# JacdacJoystick_44.net
KiCad netlist of a schematic drawn in Altium Designer
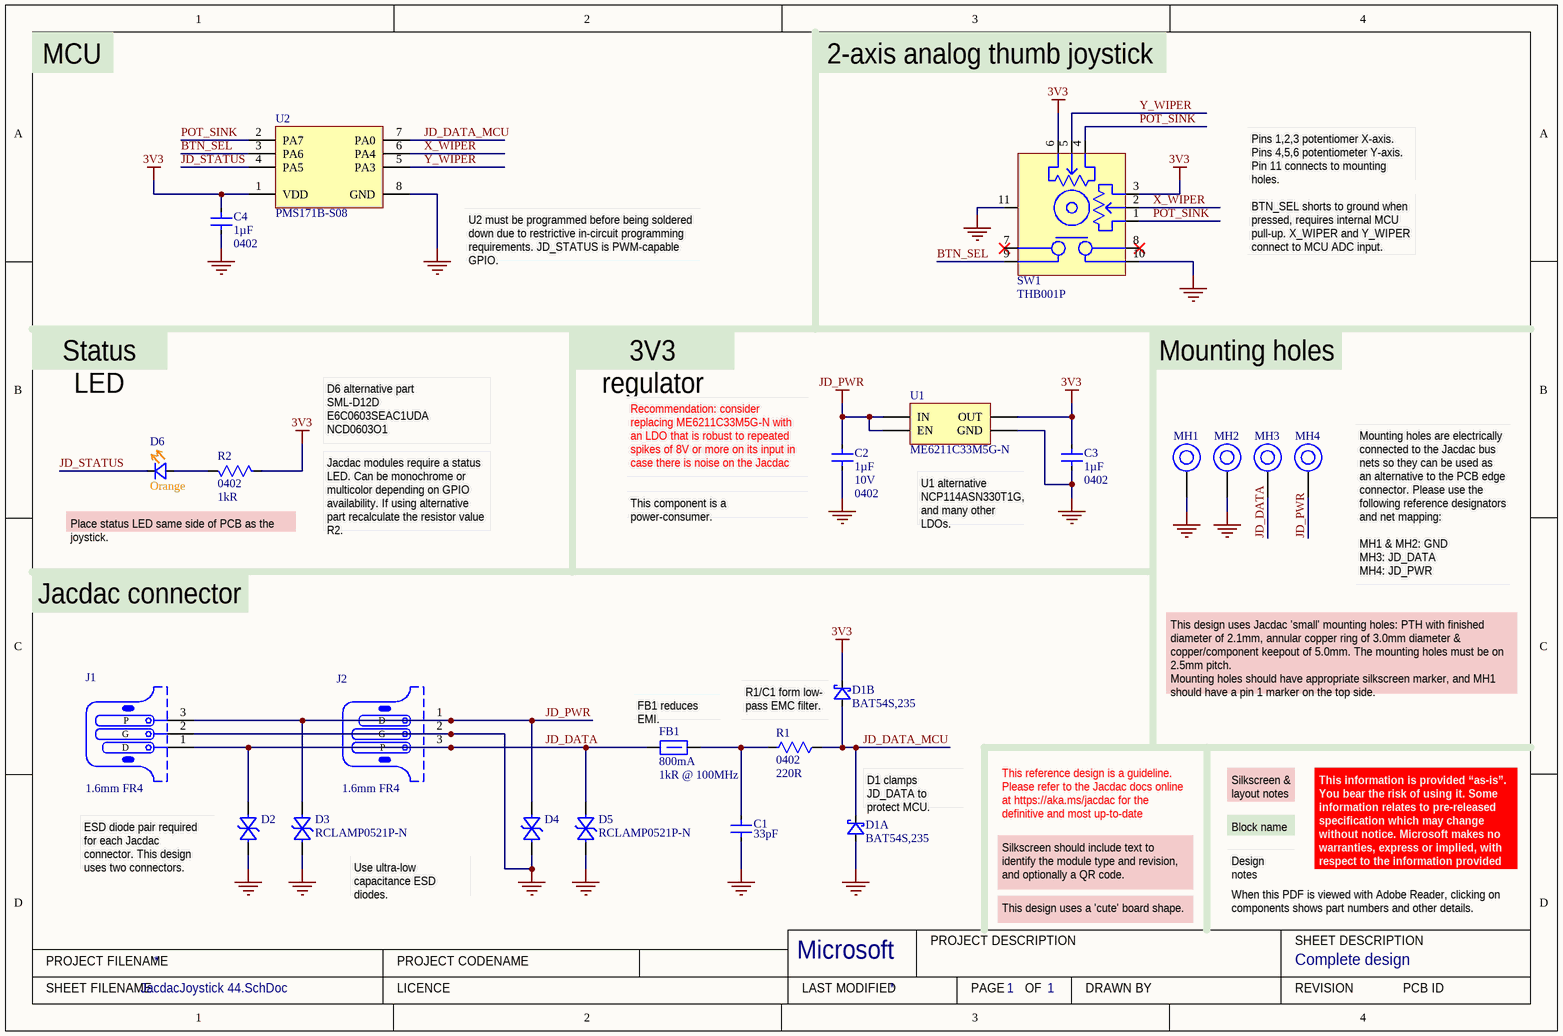
[diagram p0: JacdacJoystick 44.SchDoc]

(export (version "E")
  (design (tool "Eeschema 10.0.6"))
  (components
    (comp (ref "C1")
      (value "CL05C330JB5NNNC")
      (footprint "C0402_0.55MM - without outline")
      (description "CAP CER 33PF 50V C0G/NP0 0402")
      (fields
        (field (name "MANUFACTURER") "Samsung")
        (field (name "TOLERANCE") "5%")
        (field (name "CAPACITANCE") "33pF")
      )
      (libsource (lib "Samsung") (part "CL05C330JB5NNNC"))
    )
    (comp (ref "C2")
      (value "CL05A105KP5NNNC")
      (footprint "C0402_0.55MM - without outline")
      (description "CAP CER 1UF 10V X5R 0402")
      (fields
        (field (name "MANUFACTURER") "Samsung")
        (field (name "TOLERANCE") "10%")
        (field (name "CAPACITANCE") "1µF")
        (field (name "VOLTAGE RATING") "10V")
        (field (name "CASE CODE (IMPERIAL)") "0402")
        (field (name "CREATED") "DG")
        (field (name "CHECKED") "?")
      )
      (libsource (lib "Samsung") (part "CL05A105KP5NNNC"))
    )
    (comp (ref "C3")
      (value "CL05A105KP5NNNC")
      (footprint "C0402_0.55MM - without outline")
      (description "CAP CER 1UF 10V X5R 0402")
      (fields
        (field (name "MANUFACTURER") "Samsung")
        (field (name "TOLERANCE") "10%")
        (field (name "CAPACITANCE") "1µF")
        (field (name "CASE CODE (IMPERIAL)") "0402")
        (field (name "CREATED") "DG")
        (field (name "CHECKED") "?")
      )
      (libsource (lib "Samsung") (part "CL05A105KP5NNNC"))
    )
    (comp (ref "C4")
      (value "CL05A105KP5NNNC")
      (footprint "C0402_0.55MM - without outline")
      (description "CAP CER 1UF 10V X5R 0402")
      (fields
        (field (name "MANUFACTURER") "Samsung")
        (field (name "TOLERANCE") "10%")
        (field (name "CAPACITANCE") "1µF")
        (field (name "CASE CODE (IMPERIAL)") "0402")
        (field (name "CREATED") "DG")
        (field (name "CHECKED") "?")
      )
      (libsource (lib "Samsung") (part "CL05A105KP5NNNC"))
    )
    (comp (ref "D1")
      (value "BAT54S")
      (footprint "NXP-BAT54S-TO-236AB - without outline")
      (description "DIODE ARRAY SCHOTTKY 30V SOT23")
      (fields (field (name "MANUFACTURER") "Nexperia") (field (name "MANUFACTURER PART NUMBER") "BAT54S,235"))
      (libsource (lib "NXP") (part "BAT54S"))
    )
    (comp (ref "D2")
      (value "RCLAMP0521P-N")
      (footprint "TVS 0402 - L")
      (description "Bidirectional 5V (Max) 6V 16V 3.5A (8/20us) 0402 TVS RoHS")
      (fields
        (field (name "MANUFACTURER") "Born Semiconductor")
        (field (name "CREATED BY") "D Gakure")
        (field (name "CHECKED BY") "?")
      )
      (libsource (lib "BornSemiconductor") (part "RCLAMP0521P-N"))
    )
    (comp (ref "D3")
      (value "RCLAMP0521P-N")
      (footprint "TVS 0402 - L")
      (description "Bidirectional 5V (Max) 6V 16V 3.5A (8/20us) 0402 TVS RoHS")
      (fields
        (field (name "MANUFACTURER") "Born Semiconductor")
        (field (name "MANUFACTURER PART NUMBER") "RCLAMP0521P-N")
        (field (name "CREATED BY") "D Gakure")
        (field (name "CHECKED BY") "?")
      )
      (libsource (lib "BornSemiconductor") (part "RCLAMP0521P-N"))
    )
    (comp (ref "D4")
      (value "RCLAMP0521P-N")
      (footprint "TVS 0402 - L")
      (description "Bidirectional 5V (Max) 6V 16V 3.5A (8/20us) 0402 TVS RoHS")
      (fields
        (field (name "MANUFACTURER") "Born Semiconductor")
        (field (name "CREATED BY") "D Gakure")
        (field (name "CHECKED BY") "?")
      )
      (libsource (lib "BornSemiconductor") (part "RCLAMP0521P-N"))
    )
    (comp (ref "D5")
      (value "RCLAMP0521P-N")
      (footprint "TVS 0402 - L")
      (description "Bidirectional 5V (Max) 6V 16V 3.5A (8/20us) 0402 TVS RoHS")
      (fields
        (field (name "MANUFACTURER") "Born Semiconductor")
        (field (name "MANUFACTURER PART NUMBER") "RCLAMP0521P-N")
        (field (name "CREATED BY") "D Gakure")
        (field (name "CHECKED BY") "?")
      )
      (libsource (lib "BornSemiconductor") (part "RCLAMP0521P-N"))
    )
    (comp (ref "D6")
      (value "~")
      (footprint "0603 Orange")
      (description "LED ORANGE DIFFUSED 0603 SMD")
      (fields
        (field (name "MANUFACTURER") "Everlight Elec")
        (field (name "MANUFACTURER PART NUMBER") "19-217/S2C-AQ1R1B/3T")
        (field (name "COLOUR") "Orange")
      )
      (libsource (lib "EverlightElec") (part "19-217/S2C-AQ1R1B/3T"))
    )
    (comp (ref "FB1")
      (value "TDK MPZ1608S102ATA00")
      (footprint "TDK MPZ1608 0.8mm - without outline")
      (description "0603 1k@100MHz 0.8A chip")
      (fields
        (field (name "TOLERANCE") "25%")
        (field (name "MANUFACTURER") "TDK")
        (field (name "CURRENT RATING") "800mA")
        (field (name "IMPEDANCE") "1kR @ 100MHz")
      )
      (libsource (lib "TDK") (part "TDK MPZ1608S102ATA00"))
    )
    (comp (ref "J1")
      (value "3 pin JACDAC edge connector")
      (footprint "JACDAC_EDGE_CONNECTOR_NO_TRACES")
      (description "3 pin Jacdac edge connector 1.27mm pitch")
      (fields
        (field (name "MANUFACTURER PART NUMBER") "JACDAC_EDGE_CONNECTOR")
        (field (name "PCB TYPE") "1.6mm FR4")
        (field (name "CHECKED BY") "?")
        (field (name "CREATED BY") "D. Gakure")
      )
      (libsource (lib "generic-con") (part "Jacdac edge connector"))
    )
    (comp (ref "J2")
      (value "3 pin JACDAC edge connector")
      (footprint "JACDAC_EDGE_CONNECTOR_NO_TRACES")
      (description "3 pin Jacdac edge connector 1.27mm pitch")
      (fields
        (field (name "MANUFACTURER PART NUMBER") "JACDAC_EDGE_CONNECTOR")
        (field (name "PCB TYPE") "1.6mm FR4")
        (field (name "CHECKED BY") "?")
        (field (name "CREATED BY") "D. Gakure")
      )
      (libsource (lib "") (part "Jacdac edge connector_1"))
    )
    (comp (ref "MH1")
      (value "MH_5.0MMK_3.0MMC_2.1MMD_PTH")
      (footprint "MH_5.0MMK_3.0MMC_2.1MMD_PTH")
      (description "Mounting Hole 5.0mm keepout, 3.0mm annualar ring and 2.1mm Drill PTH")
      (libsource (lib "generic") (part "MH_5.0MMK_3.0MMC_2.1MMD_PTH"))
    )
    (comp (ref "MH2")
      (value "MH_5.0MMK_3.0MMC_2.1MMD_PTH")
      (footprint "MH_5.0MMK_3.0MMC_2.1MMD_PTH")
      (description "Mounting Hole 5.0mm keepout, 3.0mm annualar ring and 2.1mm Drill PTH")
      (libsource (lib "generic") (part "MH_5.0MMK_3.0MMC_2.1MMD_PTH"))
    )
    (comp (ref "MH3")
      (value "MH_5.0MMK_3.0MMC_2.1MMD_PTH")
      (footprint "MH_5.0MMK_3.0MMC_2.1MMD_PTH")
      (description "Mounting Hole 5.0mm keepout, 3.0mm annualar ring and 2.1mm Drill PTH")
      (libsource (lib "generic") (part "MH_5.0MMK_3.0MMC_2.1MMD_PTH"))
    )
    (comp (ref "MH4")
      (value "MH_5.0MMK_3.0MMC_2.1MMD_PTH")
      (footprint "MH_5.0MMK_3.0MMC_2.1MMD_PTH")
      (description "Mounting Hole 5.0mm keepout, 3.0mm annualar ring and 2.1mm Drill PTH")
      (libsource (lib "generic") (part "MH_5.0MMK_3.0MMC_2.1MMD_PTH"))
    )
    (comp (ref "R1")
      (value "RC0402FR-07220RL")
      (footprint "R0402 - Without outline")
      (description "RES SMD 220 OHM 1% 1/16W 0402")
      (fields
        (field (name "MANUFACTURER") "Yageo")
        (field (name "CASE CODE (IMPERIAL)") "0402")
        (field (name "RESISTANCE") "220R")
        (field (name "TOLERANCE") "1%")
        (field (name "CREATED") "D.G")
        (field (name "CHECKED") "?")
      )
      (libsource (lib "Yageo") (part "RC0402FR-07220RL"))
    )
    (comp (ref "R2")
      (value "RC0402FR-071KL")
      (footprint "R0402 - Without outline")
      (description "RES SMD 1K OHM 1% 1/16W 0402")
      (fields
        (field (name "MANUFACTURER") "Yageo")
        (field (name "CASE CODE (IMPERIAL)") "0402")
        (field (name "TOLERANCE") "1%")
        (field (name "RESISTANCE") "1kR")
        (field (name "CREATED") "D.G")
        (field (name "CHECKED") "?")
      )
      (libsource (lib "Yageo") (part "RC0402FR-071KL"))
    )
    (comp (ref "SW1")
      (value "THB001P")
      (footprint "THB001P")
      (description "Joystick, 2 - Axis Analog (Resistive) Output")
      (fields (field (name "MANUFACTURER") "ITT C&K") (field (name "MANUFACTURER PART NUMBER") "THB001P"))
      (libsource (lib "C&K") (part "THB001P"))
    )
    (comp (ref "U1")
      (value "ME6211C33M5G-N")
      (footprint "MICRONE-SOT23-5")
      (description "6V 260mV @ 200mA(typ) - - Fixed 3.3V SOT-23-5 Linear Voltage Regulators (LDO) ROHS")
      (fields
        (field (name "MANUFACTURER") "MICRONE(Nanjing Micro One Elec)")
        (field (name "MANUFACTURER PART NUMBER") "ME6211C33M5G-N")
        (field (name "CREATED") "DG")
        (field (name "CHECKED") "?")
      )
      (libsource (lib "MICRONE(NanjingMicroOneElec)") (part "ME6211C33M5G-N"))
    )
    (comp (ref "U2")
      (value "PMS171B-S08")
      (footprint "SOP-8")
      (description "8bit OTP MCU with 8-bit ADC")
      (fields (field (name "MANUFACTURER") "PADAUK") (field (name "MANUFACTURER PART NUMBER") "PMS171B-S08"))
      (libsource (lib "PADAUK") (part "PMS171B-S08"))
    )
  )
  (nets
    (net (code "1") (name "/BTN_SEL") (class "Default")
      (node (ref "SW1") (pin "9") (pinfunction "C_9") (pintype "passive"))
      (node (ref "U2") (pin "3") (pinfunction "PA6_3") (pintype "passive"))
    )
    (net (code "2") (name "/JD_DATA") (class "Default")
      (node (ref "D2") (pin "1") (pinfunction "K_1") (pintype "passive"))
      (node (ref "D5") (pin "1") (pinfunction "K_1") (pintype "passive"))
      (node (ref "FB1") (pin "1") (pinfunction "1_1") (pintype "passive"))
      (node (ref "J1") (pin "1") (pinfunction "D_1") (pintype "passive"))
      (node (ref "J2") (pin "3") (pinfunction "P_3") (pintype "passive"))
      (node (ref "MH3") (pin "1") (pinfunction "1_1") (pintype "passive"))
    )
    (net (code "3") (name "/JD_DATA_MCU") (class "Default")
      (node (ref "D1") (pin "3") (pinfunction "K_3") (pintype "passive"))
      (node (ref "R1") (pin "1") (pinfunction "1_1") (pintype "passive"))
      (node (ref "U2") (pin "7") (pinfunction "PA0_7") (pintype "passive"))
    )
    (net (code "4") (name "/JD_STATUS") (class "Default")
      (node (ref "D6") (pin "1") (pinfunction "K_1") (pintype "passive"))
      (node (ref "U2") (pin "4") (pinfunction "PA5_4") (pintype "passive"))
    )
    (net (code "5") (name "/POT_SINK") (class "Default")
      (node (ref "SW1") (pin "1") (pinfunction "VR11_1") (pintype "passive"))
      (node (ref "SW1") (pin "4") (pinfunction "VR21_4") (pintype "passive"))
      (node (ref "U2") (pin "2") (pinfunction "PA7_2") (pintype "passive"))
    )
    (net (code "6") (name "/X_WIPER") (class "Default")
      (node (ref "SW1") (pin "2") (pinfunction "VR12_2") (pintype "passive"))
      (node (ref "U2") (pin "6") (pinfunction "PA4_6") (pintype "passive"))
    )
    (net (code "7") (name "/Y_WIPER") (class "Default")
      (node (ref "SW1") (pin "5") (pinfunction "VR22_5") (pintype "passive"))
      (node (ref "U2") (pin "5") (pinfunction "PA3_5") (pintype "passive"))
    )
    (net (code "8") (name "3V3") (class "Default")
      (node (ref "C3") (pin "2") (pinfunction "2_2") (pintype "passive"))
      (node (ref "C4") (pin "2") (pinfunction "2_2") (pintype "passive"))
      (node (ref "D1") (pin "2") (pinfunction "K_2") (pintype "passive"))
      (node (ref "R2") (pin "2") (pinfunction "2_2") (pintype "passive"))
      (node (ref "SW1") (pin "3") (pinfunction "VR13_3") (pintype "passive"))
      (node (ref "SW1") (pin "6") (pinfunction "VR23_6") (pintype "passive"))
      (node (ref "U1") (pin "5") (pinfunction "OUT_5") (pintype "passive"))
      (node (ref "U2") (pin "1") (pinfunction "VDD_1") (pintype "passive"))
    )
    (net (code "9") (name "GND") (class "Default")
      (node (ref "C1") (pin "1") (pinfunction "1_1") (pintype "passive"))
      (node (ref "C2") (pin "1") (pinfunction "1_1") (pintype "passive"))
      (node (ref "C3") (pin "1") (pinfunction "1_1") (pintype "passive"))
      (node (ref "C4") (pin "1") (pinfunction "1_1") (pintype "passive"))
      (node (ref "D1") (pin "1") (pinfunction "A_1") (pintype "passive"))
      (node (ref "D2") (pin "2") (pinfunction "A_2") (pintype "passive"))
      (node (ref "D3") (pin "2") (pinfunction "A_2") (pintype "passive"))
      (node (ref "D4") (pin "2") (pinfunction "A_2") (pintype "passive"))
      (node (ref "D5") (pin "2") (pinfunction "A_2") (pintype "passive"))
      (node (ref "J1") (pin "2") (pinfunction "G_2") (pintype "passive"))
      (node (ref "J2") (pin "2") (pinfunction "G_2") (pintype "passive"))
      (node (ref "MH1") (pin "1") (pinfunction "1_1") (pintype "passive"))
      (node (ref "MH2") (pin "1") (pinfunction "1_1") (pintype "passive"))
      (node (ref "SW1") (pin "10") (pinfunction "D_10") (pintype "passive"))
      (node (ref "SW1") (pin "11") (pinfunction "MH_11") (pintype "passive"))
      (node (ref "U1") (pin "2") (pinfunction "GND_2") (pintype "passive"))
      (node (ref "U2") (pin "8") (pinfunction "GND_8") (pintype "passive"))
    )
    (net (code "10") (name "JD_PWR") (class "Default")
      (node (ref "C2") (pin "2") (pinfunction "2_2") (pintype "passive"))
      (node (ref "D3") (pin "1") (pinfunction "K_1") (pintype "passive"))
      (node (ref "D4") (pin "1") (pinfunction "K_1") (pintype "passive"))
      (node (ref "J1") (pin "3") (pinfunction "P_3") (pintype "passive"))
      (node (ref "J2") (pin "1") (pinfunction "D_1") (pintype "passive"))
      (node (ref "MH4") (pin "1") (pinfunction "1_1") (pintype "passive"))
      (node (ref "U1") (pin "1") (pinfunction "IN_1") (pintype "passive"))
      (node (ref "U1") (pin "3") (pinfunction "EN_3") (pintype "passive"))
    )
    (net (code "11") (name "Net-(C1-Pad2)") (class "Default")
      (node (ref "C1") (pin "2") (pinfunction "2_2") (pintype "passive"))
      (node (ref "FB1") (pin "2") (pinfunction "2_2") (pintype "passive"))
      (node (ref "R1") (pin "2") (pinfunction "2_2") (pintype "passive"))
    )
    (net (code "12") (name "Net-(D6-A)") (class "Default")
      (node (ref "D6") (pin "2") (pinfunction "A_2") (pintype "passive"))
      (node (ref "R2") (pin "1") (pinfunction "1_1") (pintype "passive"))
    )
    (net (code "13") (name "unconnected-(SW1-A-Pad7)") (class "Default")
      (node (ref "SW1") (pin "7") (pinfunction "A_7") (pintype "passive+no_connect"))
    )
    (net (code "14") (name "unconnected-(SW1-B-Pad8)") (class "Default")
      (node (ref "SW1") (pin "8") (pinfunction "B_8") (pintype "passive+no_connect"))
    )
  )
)
